# Schematic.net
KiCad netlist of a schematic drawn in Altium Designer
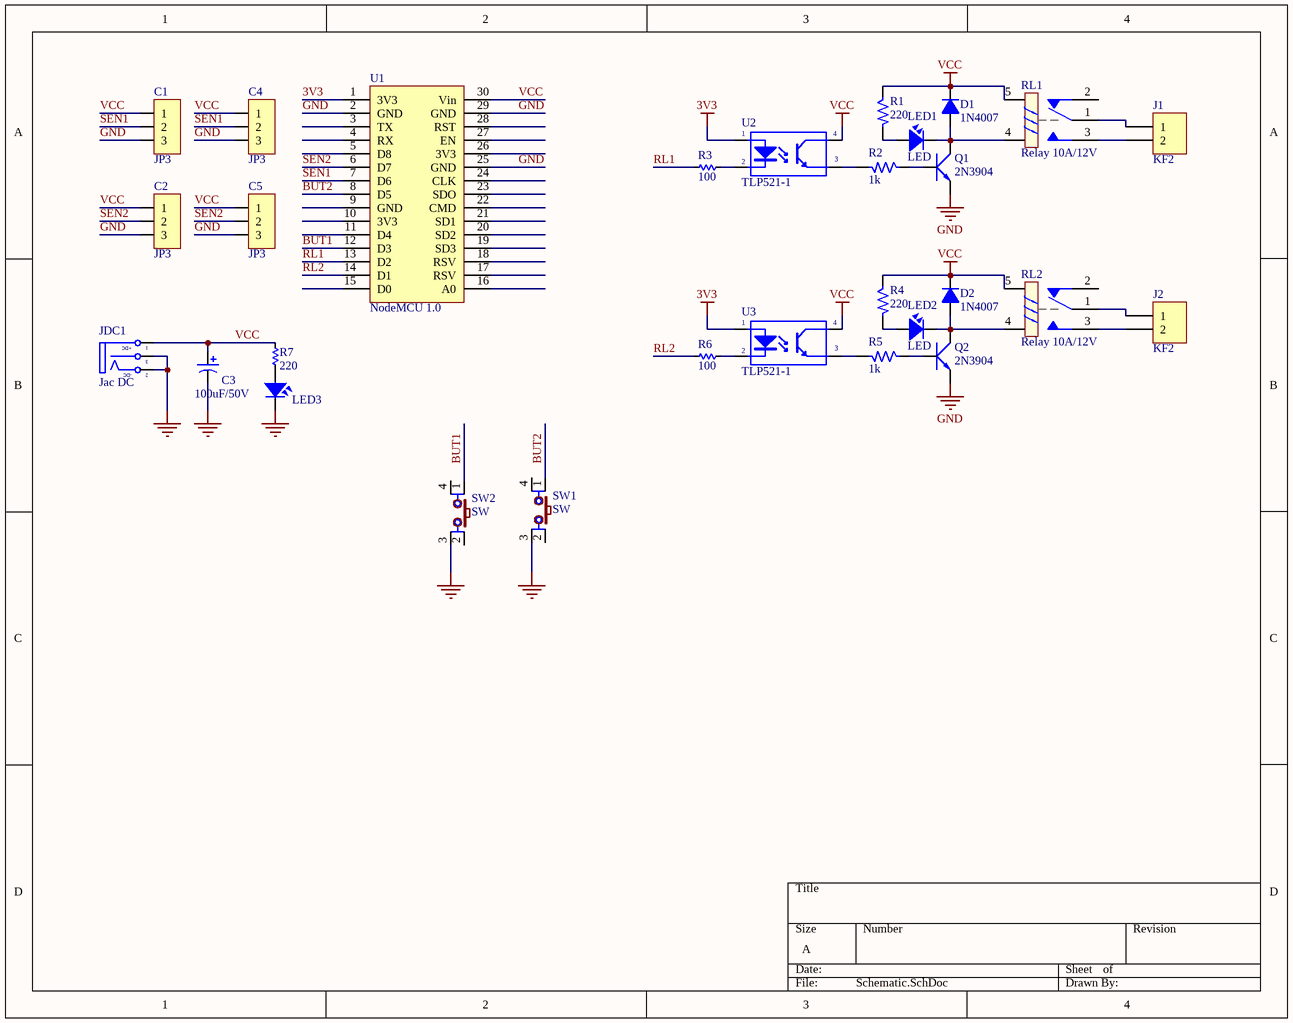
[diagram p0: Schematic.SchDoc]

(export (version "E")
  (design (tool "Eeschema 10.0.6"))
  (components
    (comp (ref "C1")
      (value "JP3")
      (footprint "JP3-C1T")
      (description "WR-PHD 2.54 mm Angled Socket Header")
      (fields
        (field (name "MANUFACTURER") "Würth Elektronik eiSos GmbH")
        (field (name "PARTNO") "613003143121")
        (field (name "CREATED BY") "Karrer Zheng")
      )
      (libsource (lib "Library") (part "JP3"))
    )
    (comp (ref "C2")
      (value "JP3")
      (footprint "JP3-C1T")
      (description "WR-PHD 2.54 mm Angled Socket Header")
      (fields
        (field (name "MANUFACTURER") "Würth Elektronik eiSos GmbH")
        (field (name "PARTNO") "613003143121")
        (field (name "CREATED BY") "Karrer Zheng")
      )
      (libsource (lib "Library") (part "JP3"))
    )
    (comp (ref "C3")
      (value "100uF/50V")
      (footprint "CE_8x12")
      (description "Cap P  470uF/16V - 100uF?35V")
      (fields (field (name "Comment") "CP3"))
      (libsource (lib "AS50") (part "CP3"))
    )
    (comp (ref "C4")
      (value "JP3")
      (footprint "JP3-D1T")
      (description "WR-PHD 2.54 mm Angled Socket Header")
      (fields
        (field (name "MANUFACTURER") "Würth Elektronik eiSos GmbH")
        (field (name "PARTNO") "613003143121")
        (field (name "CREATED BY") "Karrer Zheng")
      )
      (libsource (lib "Library") (part "JP3"))
    )
    (comp (ref "C5")
      (value "JP3")
      (footprint "JP3-D1T")
      (description "WR-PHD 2.54 mm Angled Socket Header")
      (fields
        (field (name "MANUFACTURER") "Würth Elektronik eiSos GmbH")
        (field (name "PARTNO") "613003143121")
        (field (name "CREATED BY") "Karrer Zheng")
      )
      (libsource (lib "Library") (part "JP3"))
    )
    (comp (ref "D1")
      (value "1N4007")
      (footprint "DIO-1A-SMALL")
      (description "Diode 1A")
      (libsource (lib "syhaunguyen") (part "D1A"))
    )
    (comp (ref "D2")
      (value "1N4007")
      (footprint "DIO-1A-SMALL")
      (description "Diode 1A")
      (libsource (lib "syhaunguyen") (part "D1A"))
    )
    (comp (ref "J1")
      (value "KF2")
      (footprint "KF2-5.08")
      (fields
        (field (name "MANUFACTURER") "Würth Elektronik eiSos GmbH")
        (field (name "PARTNO") "691103110002")
        (field (name "CREATED BY") "Karrer Zheng")
      )
      (libsource (lib "Library") (part "KF2"))
    )
    (comp (ref "J2")
      (value "KF2")
      (footprint "KF2-5.08")
      (fields
        (field (name "MANUFACTURER") "Würth Elektronik eiSos GmbH")
        (field (name "PARTNO") "691103110002")
        (field (name "CREATED BY") "Karrer Zheng")
      )
      (libsource (lib "Library") (part "KF2"))
    )
    (comp (ref "JDC1")
      (value "Jac DC")
      (footprint "DC0")
      (description "Jac DC input")
      (libsource (lib "Library") (part "DCIN"))
    )
    (comp (ref "LED1")
      (value "LED")
      (footprint "LED-3MM-RED")
      (description "LED Single colour Green and Red")
      (libsource (lib "syhaunguyen") (part "LED"))
    )
    (comp (ref "LED2")
      (value "LED")
      (footprint "LED-3MM-RED")
      (description "LED Single colour Green and Red")
      (libsource (lib "syhaunguyen") (part "LED"))
    )
    (comp (ref "LED3") (value "LED") (footprint "LED-3MM-RED") (libsource (lib "Library") (part "LED SMD")))
    (comp (ref "Q1")
      (value "2N3904")
      (footprint "TO92-123")
      (description "NPN 600mW, ECB")
      (libsource (lib "Library") (part "2N904"))
    )
    (comp (ref "Q2")
      (value "2N3904")
      (footprint "TO92-123")
      (description "NPN 600mW, ECB")
      (libsource (lib "Library") (part "2N904"))
    )
    (comp (ref "R1")
      (value "220")
      (footprint "RES-1/4W-SMALL")
      (description "Resistor 1/4W")
      (libsource (lib "syhaunguyen") (part "R"))
    )
    (comp (ref "R2")
      (value "1k")
      (footprint "RES-1/4W-SMALL")
      (description "Resistor 1/4W")
      (libsource (lib "syhaunguyen") (part "R"))
    )
    (comp (ref "R3")
      (value "100")
      (footprint "RES-1/4W-SMALL")
      (description "Resistor")
      (fields
        (field (name "MANUFACTURER") "Generic Components")
        (field (name "PUBLISHER") "Altium Hobart Technology Centre")
      )
      (libsource (lib "Library") (part "Res-SMD"))
    )
    (comp (ref "R4")
      (value "220")
      (footprint "RES-1/4W-SMALL")
      (description "Resistor 1/4W")
      (libsource (lib "syhaunguyen") (part "R"))
    )
    (comp (ref "R5")
      (value "1k")
      (footprint "RES-1/4W-SMALL")
      (description "Resistor 1/4W")
      (libsource (lib "syhaunguyen") (part "R"))
    )
    (comp (ref "R6")
      (value "100")
      (footprint "RES-1/4W-SMALL")
      (description "Resistor")
      (fields
        (field (name "MANUFACTURER") "Generic Components")
        (field (name "PUBLISHER") "Altium Hobart Technology Centre")
      )
      (libsource (lib "Library") (part "Res-SMD"))
    )
    (comp (ref "R7")
      (value "220")
      (footprint "RES-1/4W-SMALL")
      (description "Resistor")
      (fields
        (field (name "MANUFACTURER") "Generic Components")
        (field (name "PUBLISHER") "Altium Hobart Technology Centre")
      )
      (libsource (lib "Library") (part "Res-SMD"))
    )
    (comp (ref "RL1")
      (value "Relay 10A/12V")
      (footprint "RELAY 5")
      (description "Relay SPDT,10A - 12VDC 5 Pin")
      (libsource (lib "Library") (part "Relay 5"))
    )
    (comp (ref "RL2")
      (value "Relay 10A/12V")
      (footprint "RELAY 5")
      (description "Relay SPDT,10A - 12VDC 5 Pin")
      (libsource (lib "Library") (part "Relay 5"))
    )
    (comp (ref "SW1")
      (value "SW")
      (footprint "SW4-12x12x8")
      (description "Switch button 4 pin")
      (libsource (lib "Library") (part "SW4"))
    )
    (comp (ref "SW2")
      (value "SW")
      (footprint "SW4-12x12x8")
      (description "Switch button 4 pin")
      (libsource (lib "Library") (part "SW4"))
    )
    (comp (ref "U1")
      (value "NodeMCU 1.0")
      (footprint "NODEMCU-1.0")
      (libsource (lib "Library") (part "NodeMCU 1.0"))
    )
    (comp (ref "U2")
      (value "TLP521-1")
      (footprint "DIP4")
      (description "Single Opto")
      (libsource (lib "Library") (part "TLP521-1"))
    )
    (comp (ref "U3")
      (value "TLP521-1")
      (footprint "DIP4")
      (description "Single Opto")
      (libsource (lib "Library") (part "TLP521-1"))
    )
  )
  (nets
    (net (code "1") (name "/BUT1") (class "Default")
      (node (ref "SW2") (pin "1") (pintype "passive"))
      (node (ref "U1") (pin "12") (pinfunction "D3_12") (pintype "passive"))
    )
    (net (code "2") (name "/BUT2") (class "Default")
      (node (ref "SW1") (pin "1") (pintype "passive"))
      (node (ref "U1") (pin "8") (pinfunction "D5_8") (pintype "passive"))
    )
    (net (code "3") (name "/RL1") (class "Default")
      (node (ref "R3") (pin "2") (pinfunction "2_2") (pintype "passive"))
      (node (ref "U1") (pin "13") (pinfunction "D2_13") (pintype "passive"))
    )
    (net (code "4") (name "/RL2") (class "Default")
      (node (ref "R6") (pin "2") (pinfunction "2_2") (pintype "passive"))
      (node (ref "U1") (pin "14") (pinfunction "D1_14") (pintype "passive"))
    )
    (net (code "5") (name "/SEN1") (class "Default")
      (node (ref "C1") (pin "2") (pinfunction "2_2") (pintype "passive"))
      (node (ref "C4") (pin "2") (pinfunction "2_2") (pintype "passive"))
      (node (ref "U1") (pin "7") (pinfunction "D6_7") (pintype "passive"))
    )
    (net (code "6") (name "/SEN2") (class "Default")
      (node (ref "C2") (pin "2") (pinfunction "2_2") (pintype "passive"))
      (node (ref "C5") (pin "2") (pinfunction "2_2") (pintype "passive"))
      (node (ref "U1") (pin "6") (pinfunction "D7_6") (pintype "passive"))
    )
    (net (code "7") (name "3V3") (class "Default")
      (node (ref "U1") (pin "1") (pinfunction "3V3_1") (pintype "passive"))
      (node (ref "U2") (pin "1") (pinfunction "A_1") (pintype "passive"))
      (node (ref "U3") (pin "1") (pinfunction "A_1") (pintype "passive"))
    )
    (net (code "8") (name "GND") (class "Default")
      (node (ref "C1") (pin "3") (pinfunction "3_3") (pintype "passive"))
      (node (ref "C2") (pin "3") (pinfunction "3_3") (pintype "passive"))
      (node (ref "C3") (pin "2") (pinfunction "2_2") (pintype "passive"))
      (node (ref "C4") (pin "3") (pinfunction "3_3") (pintype "passive"))
      (node (ref "C5") (pin "3") (pinfunction "3_3") (pintype "passive"))
      (node (ref "JDC1") (pin "2") (pinfunction "TN_2") (pintype "passive"))
      (node (ref "JDC1") (pin "3") (pinfunction "S_3") (pintype "power_in"))
      (node (ref "LED3") (pin "2") (pinfunction "2_2") (pintype "passive"))
      (node (ref "Q1") (pin "1") (pinfunction "E_1") (pintype "passive"))
      (node (ref "Q2") (pin "1") (pinfunction "E_1") (pintype "passive"))
      (node (ref "SW1") (pin "3") (pinfunction "3_3") (pintype "passive"))
      (node (ref "SW2") (pin "3") (pinfunction "3_3") (pintype "passive"))
      (node (ref "U1") (pin "2") (pinfunction "GND_2") (pintype "passive"))
      (node (ref "U1") (pin "25") (pinfunction "GND_25") (pintype "passive"))
      (node (ref "U1") (pin "29") (pinfunction "GND_29") (pintype "passive"))
    )
    (net (code "9") (name "Net-(D1-A)") (class "Default")
      (node (ref "D1") (pin "1") (pinfunction "A_1") (pintype "passive"))
      (node (ref "LED1") (pin "2") (pinfunction "2_2") (pintype "passive"))
      (node (ref "Q1") (pin "3") (pinfunction "C_3") (pintype "passive"))
      (node (ref "RL1") (pin "4") (pinfunction "4_4") (pintype "passive"))
    )
    (net (code "10") (name "Net-(D2-A)") (class "Default")
      (node (ref "D2") (pin "1") (pinfunction "A_1") (pintype "passive"))
      (node (ref "LED2") (pin "2") (pinfunction "2_2") (pintype "passive"))
      (node (ref "Q2") (pin "3") (pinfunction "C_3") (pintype "passive"))
      (node (ref "RL2") (pin "4") (pinfunction "4_4") (pintype "passive"))
    )
    (net (code "11") (name "Net-(J1-Pad1)") (class "Default")
      (node (ref "J1") (pin "1") (pinfunction "1_1") (pintype "passive"))
      (node (ref "RL1") (pin "1") (pinfunction "1_1") (pintype "passive"))
    )
    (net (code "12") (name "Net-(J1-Pad2)") (class "Default")
      (node (ref "J1") (pin "2") (pinfunction "2_2") (pintype "passive"))
      (node (ref "RL1") (pin "3") (pinfunction "3_3") (pintype "passive"))
    )
    (net (code "13") (name "Net-(J2-Pad1)") (class "Default")
      (node (ref "J2") (pin "1") (pinfunction "1_1") (pintype "passive"))
      (node (ref "RL2") (pin "1") (pinfunction "1_1") (pintype "passive"))
    )
    (net (code "14") (name "Net-(J2-Pad2)") (class "Default")
      (node (ref "J2") (pin "2") (pinfunction "2_2") (pintype "passive"))
      (node (ref "RL2") (pin "3") (pinfunction "3_3") (pintype "passive"))
    )
    (net (code "15") (name "Net-(LED1-Pad1)") (class "Default")
      (node (ref "LED1") (pin "1") (pinfunction "1_1") (pintype "passive"))
      (node (ref "R1") (pin "2") (pinfunction "2_2") (pintype "passive"))
    )
    (net (code "16") (name "Net-(LED2-Pad1)") (class "Default")
      (node (ref "LED2") (pin "1") (pinfunction "1_1") (pintype "passive"))
      (node (ref "R4") (pin "2") (pinfunction "2_2") (pintype "passive"))
    )
    (net (code "17") (name "Net-(LED3-Pad1)") (class "Default")
      (node (ref "LED3") (pin "1") (pinfunction "1_1") (pintype "passive"))
      (node (ref "R7") (pin "2") (pinfunction "2_2") (pintype "passive"))
    )
    (net (code "18") (name "Net-(Q1-B)") (class "Default")
      (node (ref "Q1") (pin "2") (pinfunction "B_2") (pintype "passive"))
      (node (ref "R2") (pin "1") (pinfunction "1_1") (pintype "passive"))
    )
    (net (code "19") (name "Net-(Q2-B)") (class "Default")
      (node (ref "Q2") (pin "2") (pinfunction "B_2") (pintype "passive"))
      (node (ref "R5") (pin "1") (pinfunction "1_1") (pintype "passive"))
    )
    (net (code "20") (name "Net-(U2-E)") (class "Default")
      (node (ref "R2") (pin "2") (pinfunction "2_2") (pintype "passive"))
      (node (ref "U2") (pin "3") (pinfunction "E_3") (pintype "passive"))
    )
    (net (code "21") (name "Net-(U2-K)") (class "Default")
      (node (ref "R3") (pin "1") (pinfunction "1_1") (pintype "passive"))
      (node (ref "U2") (pin "2") (pinfunction "K_2") (pintype "passive"))
    )
    (net (code "22") (name "Net-(U3-E)") (class "Default")
      (node (ref "R5") (pin "2") (pinfunction "2_2") (pintype "passive"))
      (node (ref "U3") (pin "3") (pinfunction "E_3") (pintype "passive"))
    )
    (net (code "23") (name "Net-(U3-K)") (class "Default")
      (node (ref "R6") (pin "1") (pinfunction "1_1") (pintype "passive"))
      (node (ref "U3") (pin "2") (pinfunction "K_2") (pintype "passive"))
    )
    (net (code "24") (name "VCC") (class "Default")
      (node (ref "C1") (pin "1") (pinfunction "1_1") (pintype "passive"))
      (node (ref "C2") (pin "1") (pinfunction "1_1") (pintype "passive"))
      (node (ref "C3") (pin "1") (pinfunction "1_1") (pintype "passive"))
      (node (ref "C4") (pin "1") (pinfunction "1_1") (pintype "passive"))
      (node (ref "C5") (pin "1") (pinfunction "1_1") (pintype "passive"))
      (node (ref "D1") (pin "2") (pinfunction "K_2") (pintype "passive"))
      (node (ref "D2") (pin "2") (pinfunction "K_2") (pintype "passive"))
      (node (ref "JDC1") (pin "1") (pinfunction "T_1") (pintype "passive"))
      (node (ref "R1") (pin "1") (pinfunction "1_1") (pintype "passive"))
      (node (ref "R4") (pin "1") (pinfunction "1_1") (pintype "passive"))
      (node (ref "R7") (pin "1") (pinfunction "1_1") (pintype "passive"))
      (node (ref "RL1") (pin "5") (pinfunction "5_5") (pintype "passive"))
      (node (ref "RL2") (pin "5") (pinfunction "5_5") (pintype "passive"))
      (node (ref "U1") (pin "30") (pinfunction "Vin_30") (pintype "passive"))
      (node (ref "U2") (pin "4") (pinfunction "C_4") (pintype "passive"))
      (node (ref "U3") (pin "4") (pinfunction "C_4") (pintype "passive"))
    )
    (net (code "25") (name "unconnected-(RL1-Pad2)") (class "Default")
      (node (ref "RL1") (pin "2") (pinfunction "2_2") (pintype "passive"))
    )
    (net (code "26") (name "unconnected-(RL2-Pad2)") (class "Default")
      (node (ref "RL2") (pin "2") (pinfunction "2_2") (pintype "passive"))
    )
    (net (code "27") (name "unconnected-(SW1-Pad2)") (class "Default")
      (node (ref "SW1") (pin "2") (pinfunction "2_2") (pintype "passive"))
    )
    (net (code "28") (name "unconnected-(SW1-Pad4)") (class "Default")
      (node (ref "SW1") (pin "4") (pinfunction "4_4") (pintype "passive"))
    )
    (net (code "29") (name "unconnected-(SW2-Pad2)") (class "Default")
      (node (ref "SW2") (pin "2") (pinfunction "2_2") (pintype "passive"))
    )
    (net (code "30") (name "unconnected-(SW2-Pad4)") (class "Default")
      (node (ref "SW2") (pin "4") (pinfunction "4_4") (pintype "passive"))
    )
    (net (code "31") (name "unconnected-(U1-3V3-Pad10)") (class "Default")
      (node (ref "U1") (pin "10") (pinfunction "3V3_10") (pintype "passive"))
    )
    (net (code "32") (name "unconnected-(U1-3V3-Pad26)") (class "Default")
      (node (ref "U1") (pin "26") (pinfunction "3V3_26") (pintype "passive"))
    )
    (net (code "33") (name "unconnected-(U1-A0-Pad16)") (class "Default")
      (node (ref "U1") (pin "16") (pinfunction "A0_16") (pintype "passive"))
    )
    (net (code "34") (name "unconnected-(U1-CLK-Pad24)") (class "Default")
      (node (ref "U1") (pin "24") (pinfunction "CLK_24") (pintype "passive"))
    )
    (net (code "35") (name "unconnected-(U1-CMD-Pad22)") (class "Default")
      (node (ref "U1") (pin "22") (pinfunction "CMD_22") (pintype "passive"))
    )
    (net (code "36") (name "unconnected-(U1-D0-Pad15)") (class "Default")
      (node (ref "U1") (pin "15") (pinfunction "D0_15") (pintype "passive"))
    )
    (net (code "37") (name "unconnected-(U1-D4-Pad11)") (class "Default")
      (node (ref "U1") (pin "11") (pinfunction "D4_11") (pintype "passive"))
    )
    (net (code "38") (name "unconnected-(U1-D8-Pad5)") (class "Default")
      (node (ref "U1") (pin "5") (pinfunction "D8_5") (pintype "passive"))
    )
    (net (code "39") (name "unconnected-(U1-EN-Pad27)") (class "Default")
      (node (ref "U1") (pin "27") (pinfunction "EN_27") (pintype "passive"))
    )
    (net (code "40") (name "unconnected-(U1-GND-Pad9)") (class "Default")
      (node (ref "U1") (pin "9") (pinfunction "GND_9") (pintype "passive"))
    )
    (net (code "41") (name "unconnected-(U1-RST-Pad28)") (class "Default")
      (node (ref "U1") (pin "28") (pinfunction "RST_28") (pintype "passive"))
    )
    (net (code "42") (name "unconnected-(U1-RSV-Pad17)") (class "Default")
      (node (ref "U1") (pin "17") (pinfunction "RSV_17") (pintype "passive"))
    )
    (net (code "43") (name "unconnected-(U1-RSV-Pad18)") (class "Default")
      (node (ref "U1") (pin "18") (pinfunction "RSV_18") (pintype "passive"))
    )
    (net (code "44") (name "unconnected-(U1-RX-Pad4)") (class "Default")
      (node (ref "U1") (pin "4") (pinfunction "RX_4") (pintype "passive"))
    )
    (net (code "45") (name "unconnected-(U1-SD1-Pad21)") (class "Default")
      (node (ref "U1") (pin "21") (pinfunction "SD1_21") (pintype "passive"))
    )
    (net (code "46") (name "unconnected-(U1-SD2-Pad20)") (class "Default")
      (node (ref "U1") (pin "20") (pinfunction "SD2_20") (pintype "passive"))
    )
    (net (code "47") (name "unconnected-(U1-SD3-Pad19)") (class "Default")
      (node (ref "U1") (pin "19") (pinfunction "SD3_19") (pintype "passive"))
    )
    (net (code "48") (name "unconnected-(U1-SDO-Pad23)") (class "Default")
      (node (ref "U1") (pin "23") (pinfunction "SDO_23") (pintype "passive"))
    )
    (net (code "49") (name "unconnected-(U1-TX-Pad3)") (class "Default")
      (node (ref "U1") (pin "3") (pinfunction "TX_3") (pintype "passive"))
    )
  )
)
